# MCU.net
KiCad netlist of a schematic drawn in Altium Designer
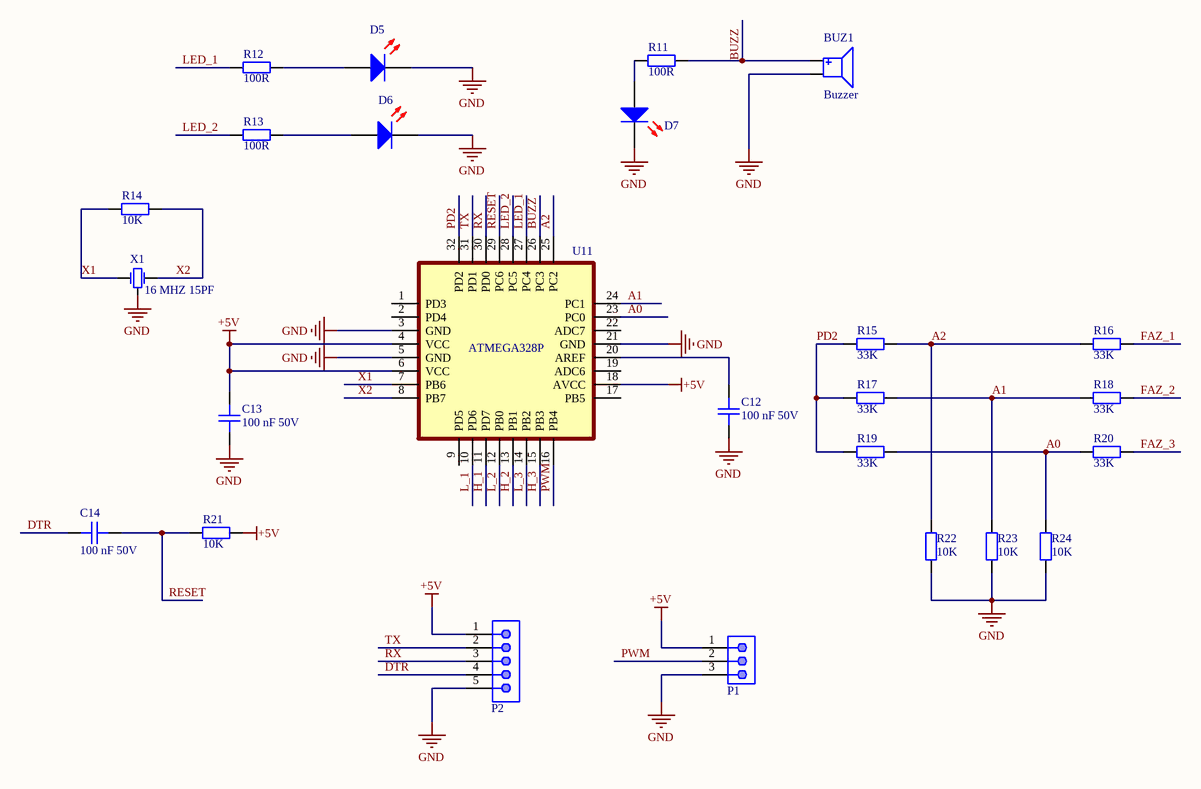
[diagram p0: MCU.SchDoc]

(export (version "E")
  (design (tool "Eeschema 10.0.6"))
  (components
    (comp (ref "BUZ1")
      (value "BUZZER MAGN 3.6V 7.5X7.5MM SMD")
      (footprint "BUZ: CMT-7525")
      (fields (field (name "DEGER") "Buzzer"))
      (libsource (lib "ESC") (part "Buzzer(CMT-7525-80-SMT-TR)"))
    )
    (comp (ref "C12")
      (value "CAP CER 0.1UF 50V X7R 0805")
      (footprint "CAP-0805(2012)")
      (description "0.1 µF ±10% 50V Ceramic Capacitor X7R 0805 (2012 Metric)")
      (fields (field (name "DEGER") "100 nF 50V"))
      (libsource (lib "ESC") (part "100nF 50V 0805"))
    )
    (comp (ref "C13")
      (value "CAP CER 0.1UF 50V X7R 0805")
      (footprint "CAP-0805(2012)")
      (description "0.1 µF ±10% 50V Ceramic Capacitor X7R 0805 (2012 Metric)")
      (fields (field (name "DEGER") "100 nF 50V"))
      (libsource (lib "ESC") (part "100nF 50V 0805"))
    )
    (comp (ref "C14")
      (value "CAP CER 0.1UF 50V X7R 0805")
      (footprint "CAP-0805(2012)")
      (description "0.1 µF ±10% 50V Ceramic Capacitor X7R 0805 (2012 Metric)")
      (fields (field (name "DEGER") "100 nF 50V"))
      (libsource (lib "ESC") (part "100nF 50V 0805"))
    )
    (comp (ref "D5")
      (value "Red 645nm LED Indication - Discrete 1.8V 0805")
      (footprint "SMD: LED 0805/2012 RED")
      (description "LED RED DIFFUSED 0805 SMD")
      (libsource (lib "ESC") (part "LED_Kırmızı"))
    )
    (comp (ref "D6")
      (value "Red 645nm LED Indication - Discrete 1.8V 0805")
      (footprint "SMD: LED 0805/2012 RED")
      (description "LED RED DIFFUSED 0805 SMD")
      (libsource (lib "ESC") (part "LED_Kırmızı"))
    )
    (comp (ref "D7")
      (value "Red 645nm LED Indication - Discrete 1.8V 0805")
      (footprint "SMD: LED 0805/2012 RED")
      (description "LED RED DIFFUSED 0805 SMD")
      (libsource (lib "ESC") (part "LED_Kırmızı"))
    )
    (comp (ref "P1")
      (value "WR-PHD 2.54 mm Angled Socket Header")
      (footprint "PWM_CONN")
      (libsource (lib "ESC") (part "HDR(1X3)"))
    )
    (comp (ref "P2")
      (value "WR-PHD 2.54 mm Angled Socket Header")
      (footprint "TTL_CONN_5")
      (libsource (lib "ESC") (part "HDR(1X5)"))
    )
    (comp (ref "R11")
      (value "RES SMD 100 OHM 1% 1/8W 0805")
      (footprint "RES-0805")
      (description "100 Ohms ±1% 0.125W, 1/8W Chip Resistor 0805 (2012 Metric) Moisture Resistant Thick Film")
      (fields (field (name "DEGER") "100R"))
      (libsource (lib "ESC") (part "100R 0805"))
    )
    (comp (ref "R12")
      (value "RES SMD 100 OHM 1% 1/8W 0805")
      (footprint "RES-0805")
      (description "100 Ohms ±1% 0.125W, 1/8W Chip Resistor 0805 (2012 Metric) Moisture Resistant Thick Film")
      (fields (field (name "DEGER") "100R"))
      (libsource (lib "ESC") (part "100R 0805"))
    )
    (comp (ref "R13")
      (value "RES SMD 100 OHM 1% 1/8W 0805")
      (footprint "RES-0805")
      (description "100 Ohms ±1% 0.125W, 1/8W Chip Resistor 0805 (2012 Metric) Moisture Resistant Thick Film")
      (fields (field (name "DEGER") "100R"))
      (libsource (lib "ESC") (part "100R 0805"))
    )
    (comp (ref "R14")
      (value "RES SMD 10K OHM 1% 1/8W 0805")
      (footprint "RES-0805")
      (description "10 kOhms ±1% 0.125W, 1/8W Chip Resistor 0805 (2012 Metric) Moisture Resistant Thick Film")
      (fields (field (name "DEGER") "10K"))
      (libsource (lib "") (part "10K 0805_1"))
    )
    (comp (ref "R15")
      (value "RES SMD 33K OHM 1% 1/8W 0805")
      (footprint "RES-0805")
      (description "33 kOhms ±1% 0.125W, 1/8W Chip Resistor 0805 (2012 Metric) Moisture Resistant Thick Film")
      (fields (field (name "DEGER") "33K"))
      (libsource (lib "ESC") (part "33K 0805"))
    )
    (comp (ref "R16")
      (value "RES SMD 33K OHM 1% 1/8W 0805")
      (footprint "RES-0805")
      (description "33 kOhms ±1% 0.125W, 1/8W Chip Resistor 0805 (2012 Metric) Moisture Resistant Thick Film")
      (fields (field (name "DEGER") "33K"))
      (libsource (lib "ESC") (part "33K 0805"))
    )
    (comp (ref "R17")
      (value "RES SMD 33K OHM 1% 1/8W 0805")
      (footprint "RES-0805")
      (description "33 kOhms ±1% 0.125W, 1/8W Chip Resistor 0805 (2012 Metric) Moisture Resistant Thick Film")
      (fields (field (name "DEGER") "33K"))
      (libsource (lib "ESC") (part "33K 0805"))
    )
    (comp (ref "R18")
      (value "RES SMD 33K OHM 1% 1/8W 0805")
      (footprint "RES-0805")
      (description "33 kOhms ±1% 0.125W, 1/8W Chip Resistor 0805 (2012 Metric) Moisture Resistant Thick Film")
      (fields (field (name "DEGER") "33K"))
      (libsource (lib "ESC") (part "33K 0805"))
    )
    (comp (ref "R19")
      (value "RES SMD 33K OHM 1% 1/8W 0805")
      (footprint "RES-0805")
      (description "33 kOhms ±1% 0.125W, 1/8W Chip Resistor 0805 (2012 Metric) Moisture Resistant Thick Film")
      (fields (field (name "DEGER") "33K"))
      (libsource (lib "ESC") (part "33K 0805"))
    )
    (comp (ref "R20")
      (value "RES SMD 33K OHM 1% 1/8W 0805")
      (footprint "RES-0805")
      (description "33 kOhms ±1% 0.125W, 1/8W Chip Resistor 0805 (2012 Metric) Moisture Resistant Thick Film")
      (fields (field (name "DEGER") "33K"))
      (libsource (lib "ESC") (part "33K 0805"))
    )
    (comp (ref "R21")
      (value "RES SMD 10K OHM 1% 1/8W 0805")
      (footprint "RES-0805")
      (description "10 kOhms ±1% 0.125W, 1/8W Chip Resistor 0805 (2012 Metric) Moisture Resistant Thick Film")
      (fields (field (name "DEGER") "10K"))
      (libsource (lib "") (part "10K 0805_1"))
    )
    (comp (ref "R22")
      (value "RES SMD 10K OHM 1% 1/8W 0805")
      (footprint "RES-0805")
      (description "10 kOhms ±1% 0.125W, 1/8W Chip Resistor 0805 (2012 Metric) Moisture Resistant Thick Film")
      (fields (field (name "DEGER") "10K"))
      (libsource (lib "ESC") (part "10K 0805"))
    )
    (comp (ref "R23")
      (value "RES SMD 10K OHM 1% 1/8W 0805")
      (footprint "RES-0805")
      (description "10 kOhms ±1% 0.125W, 1/8W Chip Resistor 0805 (2012 Metric) Moisture Resistant Thick Film")
      (fields (field (name "DEGER") "10K"))
      (libsource (lib "ESC") (part "10K 0805"))
    )
    (comp (ref "R24")
      (value "RES SMD 10K OHM 1% 1/8W 0805")
      (footprint "RES-0805")
      (description "10 kOhms ±1% 0.125W, 1/8W Chip Resistor 0805 (2012 Metric) Moisture Resistant Thick Film")
      (fields (field (name "DEGER") "10K"))
      (libsource (lib "ESC") (part "10K 0805"))
    )
    (comp (ref "U11")
      (value "IC MCU 8BIT 32KB FLASH 32TQFP")
      (footprint "TQFP32")
      (description "AVR AVR® ATmega Microcontroller IC 8-Bit 20MHz 32KB (16K x 16) FLASH 32-TQFP (7x7)")
      (fields (field (name "DEGER") "ATMEGA328P"))
      (libsource (lib "ESC") (part "ATMEGA328P"))
    )
    (comp (ref "X1")
      (value "CERAMIC RES 16.0000MHZ 15PF SMD")
      (footprint "CRYSTAL_16MHZ(CTSE16)")
      (description "16MHz Ceramic Resonator Built in Capacitor 15pF ±0.3%  -20°C ~ 80°C Surface Mount")
      (fields (field (name "DEGER") "16 MHZ 15PF"))
      (libsource (lib "ESC") (part "CRYSTAL 16.0000MHZ(CSTCE16M0V53-R0)"))
    )
  )
  (nets
    (net (code "1") (name "+5V") (class "Default")
      (node (ref "C13") (pin "2") (pinfunction "2_2") (pintype "passive"))
      (node (ref "P1") (pin "1") (pinfunction "1_1") (pintype "passive"))
      (node (ref "P2") (pin "1") (pinfunction "1_1") (pintype "passive"))
      (node (ref "R21") (pin "2") (pinfunction "2_2") (pintype "passive"))
      (node (ref "U11") (pin "18") (pinfunction "AVCC_18") (pintype "passive"))
      (node (ref "U11") (pin "4") (pinfunction "VCC_4") (pintype "passive"))
      (node (ref "U11") (pin "6") (pinfunction "VCC_6") (pintype "passive"))
    )
    (net (code "2") (name "/A0") (class "Default")
      (node (ref "R19") (pin "2") (pinfunction "2_2") (pintype "passive"))
      (node (ref "R20") (pin "1") (pinfunction "1_1") (pintype "passive"))
      (node (ref "R24") (pin "2") (pinfunction "2_2") (pintype "passive"))
      (node (ref "U11") (pin "23") (pinfunction "PC0_23") (pintype "passive"))
    )
    (net (code "3") (name "/A1") (class "Default")
      (node (ref "R17") (pin "2") (pinfunction "2_2") (pintype "passive"))
      (node (ref "R18") (pin "1") (pinfunction "1_1") (pintype "passive"))
      (node (ref "R23") (pin "2") (pinfunction "2_2") (pintype "passive"))
      (node (ref "U11") (pin "24") (pinfunction "PC1_24") (pintype "passive"))
    )
    (net (code "4") (name "/A2") (class "Default")
      (node (ref "R15") (pin "2") (pinfunction "2_2") (pintype "passive"))
      (node (ref "R16") (pin "1") (pinfunction "1_1") (pintype "passive"))
      (node (ref "R22") (pin "2") (pinfunction "2_2") (pintype "passive"))
      (node (ref "U11") (pin "25") (pinfunction "PC2_25") (pintype "passive"))
    )
    (net (code "5") (name "/BUZZ") (class "Default")
      (node (ref "BUZ1") (pin "1") (pinfunction "Positive_1") (pintype "passive"))
      (node (ref "R11") (pin "2") (pinfunction "2_2") (pintype "passive"))
      (node (ref "U11") (pin "26") (pinfunction "PC3_26") (pintype "passive"))
    )
    (net (code "6") (name "/DTR") (class "Default")
      (node (ref "C14") (pin "1") (pinfunction "1_1") (pintype "passive"))
      (node (ref "P2") (pin "4") (pinfunction "4_4") (pintype "passive"))
    )
    (net (code "7") (name "/FAZ_1") (class "Default")
      (node (ref "R16") (pin "2") (pinfunction "2_2") (pintype "passive"))
    )
    (net (code "8") (name "/FAZ_2") (class "Default")
      (node (ref "R18") (pin "2") (pinfunction "2_2") (pintype "passive"))
    )
    (net (code "9") (name "/FAZ_3") (class "Default")
      (node (ref "R20") (pin "2") (pinfunction "2_2") (pintype "passive"))
    )
    (net (code "10") (name "/H_1") (class "Default")
      (node (ref "U11") (pin "11") (pinfunction "PD7_11") (pintype "passive"))
    )
    (net (code "11") (name "/H_2") (class "Default")
      (node (ref "U11") (pin "13") (pinfunction "PB1_13") (pintype "passive"))
    )
    (net (code "12") (name "/H_3") (class "Default")
      (node (ref "U11") (pin "15") (pinfunction "PB3_15") (pintype "passive"))
    )
    (net (code "13") (name "/LED_1") (class "Default")
      (node (ref "R12") (pin "1") (pinfunction "1_1") (pintype "passive"))
      (node (ref "U11") (pin "27") (pinfunction "PC4_27") (pintype "passive"))
    )
    (net (code "14") (name "/LED_2") (class "Default")
      (node (ref "R13") (pin "1") (pinfunction "1_1") (pintype "passive"))
      (node (ref "U11") (pin "28") (pinfunction "PC5_28") (pintype "passive"))
    )
    (net (code "15") (name "/L_1") (class "Default")
      (node (ref "U11") (pin "10") (pinfunction "PD6_10") (pintype "passive"))
    )
    (net (code "16") (name "/L_2") (class "Default")
      (node (ref "U11") (pin "12") (pinfunction "PB0_12") (pintype "passive"))
    )
    (net (code "17") (name "/L_3") (class "Default")
      (node (ref "U11") (pin "14") (pinfunction "PB2_14") (pintype "passive"))
    )
    (net (code "18") (name "/PD2") (class "Default")
      (node (ref "R15") (pin "1") (pinfunction "1_1") (pintype "passive"))
      (node (ref "R17") (pin "1") (pinfunction "1_1") (pintype "passive"))
      (node (ref "R19") (pin "1") (pinfunction "1_1") (pintype "passive"))
      (node (ref "U11") (pin "32") (pinfunction "PD2_32") (pintype "passive"))
    )
    (net (code "19") (name "/PWM") (class "Default")
      (node (ref "P1") (pin "2") (pinfunction "2_2") (pintype "passive"))
      (node (ref "U11") (pin "16") (pinfunction "PB4_16") (pintype "passive"))
    )
    (net (code "20") (name "/RESET") (class "Default")
      (node (ref "C14") (pin "2") (pinfunction "2_2") (pintype "passive"))
      (node (ref "R21") (pin "1") (pinfunction "1_1") (pintype "passive"))
      (node (ref "U11") (pin "29") (pinfunction "PC6_29") (pintype "passive"))
    )
    (net (code "21") (name "/RX") (class "Default")
      (node (ref "P2") (pin "3") (pinfunction "3_3") (pintype "passive"))
      (node (ref "U11") (pin "30") (pinfunction "PD0_30") (pintype "passive"))
    )
    (net (code "22") (name "/TX") (class "Default")
      (node (ref "P2") (pin "2") (pinfunction "2_2") (pintype "passive"))
      (node (ref "U11") (pin "31") (pinfunction "PD1_31") (pintype "passive"))
    )
    (net (code "23") (name "/X1") (class "Default")
      (node (ref "R14") (pin "1") (pinfunction "1_1") (pintype "passive"))
      (node (ref "U11") (pin "7") (pinfunction "PB6_7") (pintype "passive"))
      (node (ref "X1") (pin "1") (pinfunction "OSC1_1") (pintype "passive"))
    )
    (net (code "24") (name "/X2") (class "Default")
      (node (ref "R14") (pin "2") (pinfunction "2_2") (pintype "passive"))
      (node (ref "U11") (pin "8") (pinfunction "PB7_8") (pintype "passive"))
      (node (ref "X1") (pin "3") (pinfunction "OSC2_3") (pintype "passive"))
    )
    (net (code "25") (name "GND") (class "Default")
      (node (ref "BUZ1") (pin "2") (pinfunction "Negative_2") (pintype "passive"))
      (node (ref "C12") (pin "1") (pinfunction "1_1") (pintype "passive"))
      (node (ref "C13") (pin "1") (pinfunction "1_1") (pintype "passive"))
      (node (ref "D5") (pin "2") (pinfunction "K_2") (pintype "passive"))
      (node (ref "D6") (pin "2") (pinfunction "K_2") (pintype "passive"))
      (node (ref "D7") (pin "2") (pinfunction "K_2") (pintype "passive"))
      (node (ref "P1") (pin "3") (pinfunction "3_3") (pintype "passive"))
      (node (ref "P2") (pin "5") (pinfunction "5_5") (pintype "passive"))
      (node (ref "R22") (pin "1") (pinfunction "1_1") (pintype "passive"))
      (node (ref "R23") (pin "1") (pinfunction "1_1") (pintype "passive"))
      (node (ref "R24") (pin "1") (pinfunction "1_1") (pintype "passive"))
      (node (ref "U11") (pin "21") (pinfunction "GND_21") (pintype "passive"))
      (node (ref "U11") (pin "3") (pinfunction "GND_3") (pintype "passive"))
      (node (ref "U11") (pin "5") (pinfunction "GND_5") (pintype "passive"))
      (node (ref "X1") (pin "2") (pinfunction "GND_2") (pintype "passive"))
    )
    (net (code "26") (name "Net-(D5-A)") (class "Default")
      (node (ref "D5") (pin "1") (pinfunction "A_1") (pintype "passive"))
      (node (ref "R12") (pin "2") (pinfunction "2_2") (pintype "passive"))
    )
    (net (code "27") (name "Net-(D6-A)") (class "Default")
      (node (ref "D6") (pin "1") (pinfunction "A_1") (pintype "passive"))
      (node (ref "R13") (pin "2") (pinfunction "2_2") (pintype "passive"))
    )
    (net (code "28") (name "Net-(D7-A)") (class "Default")
      (node (ref "D7") (pin "1") (pinfunction "A_1") (pintype "passive"))
      (node (ref "R11") (pin "1") (pinfunction "1_1") (pintype "passive"))
    )
    (net (code "29") (name "Net-(U11-AREF)") (class "Default")
      (node (ref "C12") (pin "2") (pinfunction "2_2") (pintype "passive"))
      (node (ref "U11") (pin "20") (pinfunction "AREF_20") (pintype "passive"))
    )
    (net (code "30") (name "unconnected-(U11-ADC6-Pad19)") (class "Default")
      (node (ref "U11") (pin "19") (pinfunction "ADC6_19") (pintype "passive"))
    )
    (net (code "31") (name "unconnected-(U11-ADC7-Pad22)") (class "Default")
      (node (ref "U11") (pin "22") (pinfunction "ADC7_22") (pintype "passive"))
    )
    (net (code "32") (name "unconnected-(U11-PB5-Pad17)") (class "Default")
      (node (ref "U11") (pin "17") (pinfunction "PB5_17") (pintype "passive"))
    )
    (net (code "33") (name "unconnected-(U11-PD3-Pad1)") (class "Default")
      (node (ref "U11") (pin "1") (pinfunction "PD3_1") (pintype "passive"))
    )
    (net (code "34") (name "unconnected-(U11-PD4-Pad2)") (class "Default")
      (node (ref "U11") (pin "2") (pinfunction "PD4_2") (pintype "passive"))
    )
    (net (code "35") (name "unconnected-(U11-PD5-Pad9)") (class "Default")
      (node (ref "U11") (pin "9") (pinfunction "PD5_9") (pintype "passive"))
    )
  )
)
